# RC_MUX.net
KiCad netlist of a schematic drawn in EAGLE
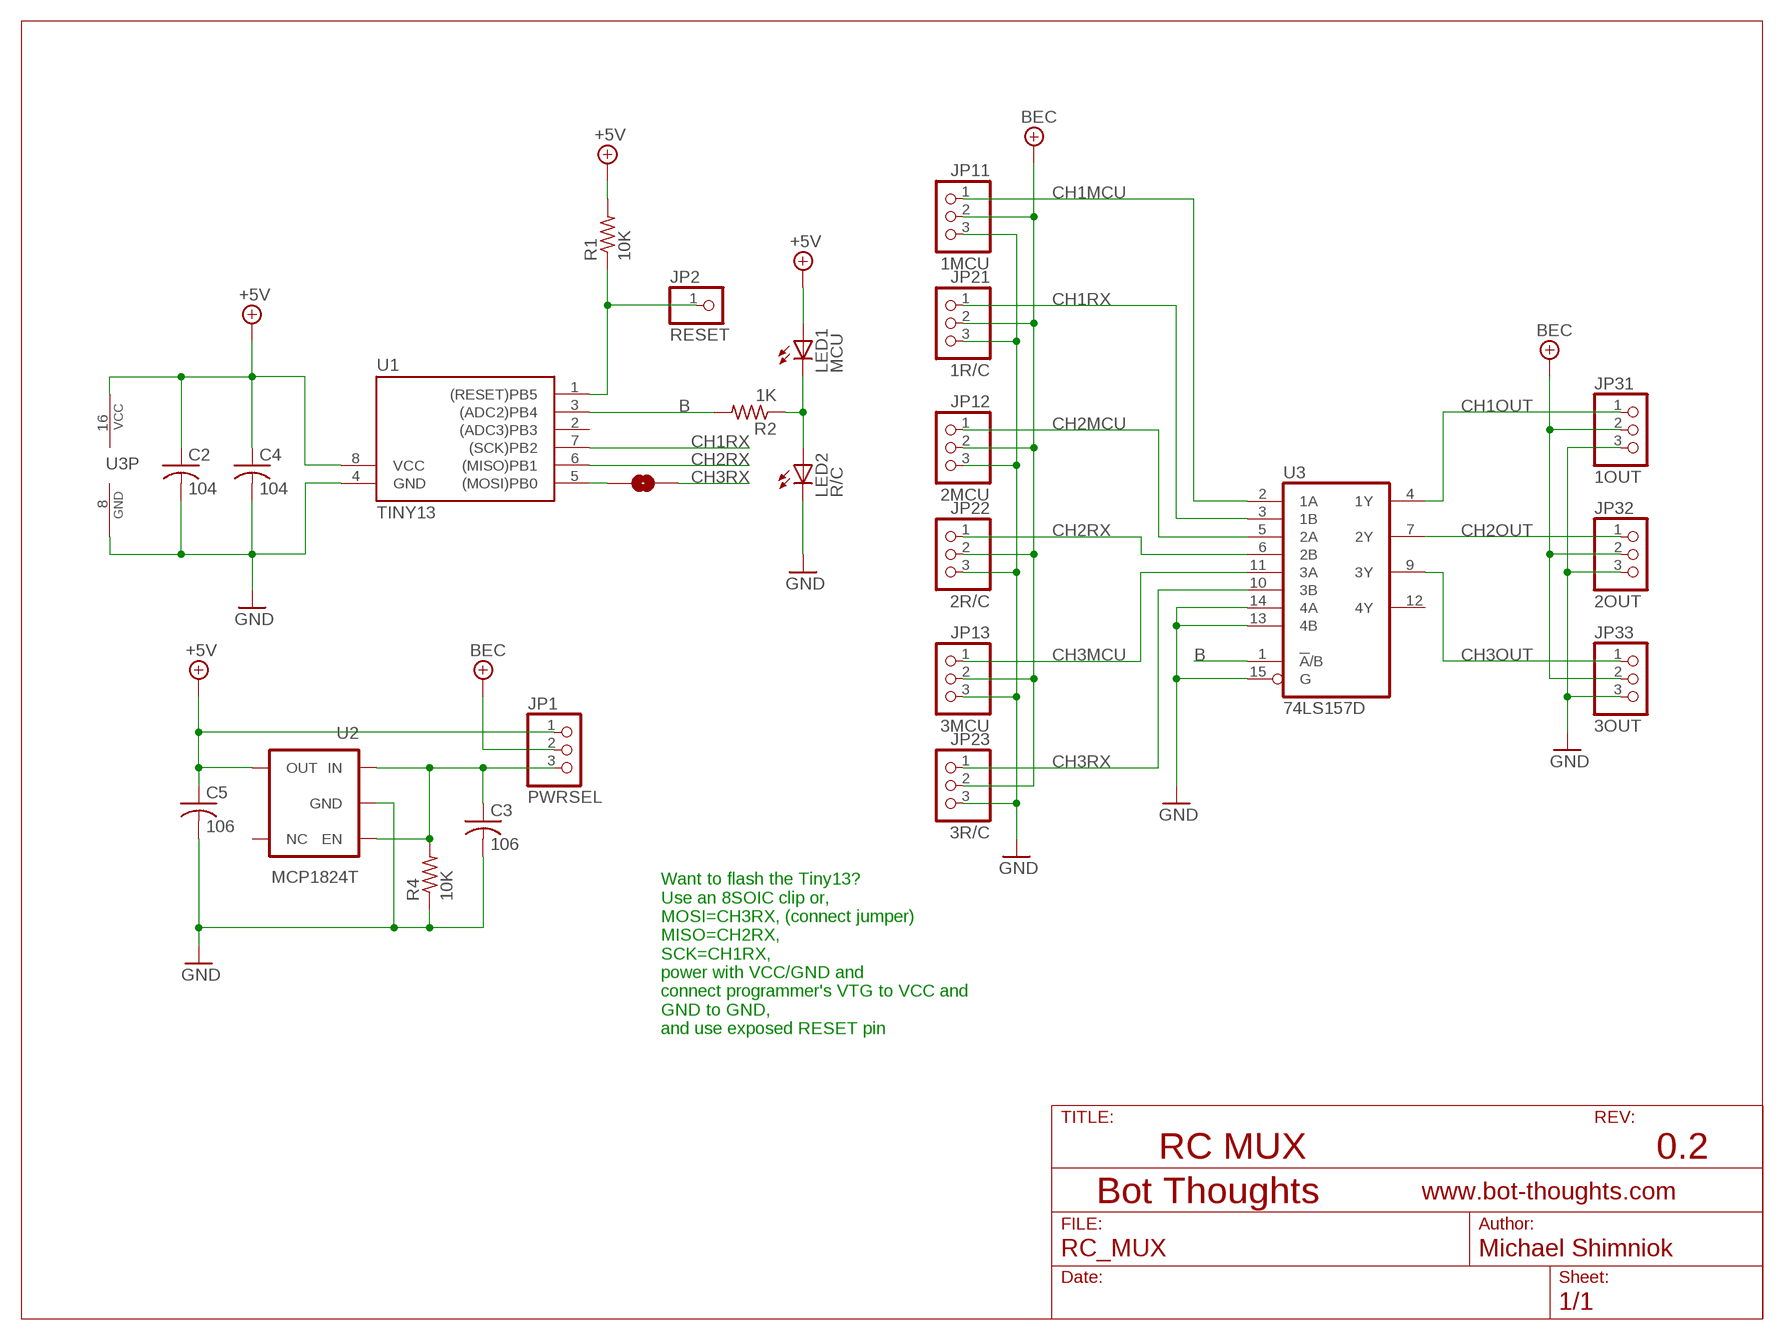
[diagram p0: schematic, sheet 1]

(export (version "E")
  (design (tool "Eeschema 10.0.6"))
  (components
    (comp (ref "C2")
      (value "104")
      (footprint "eagle-import:C0603")
      (fields (field (name "PARTNO") "C1608X7R1E104K080AA"))
      (libsource (lib "eagle-import") (part "C-USC0603"))
    )
    (comp (ref "C3")
      (value "106")
      (footprint "eagle-import:C0603")
      (fields (field (name "PARTNO") "CL10A106MP8NNNC"))
      (libsource (lib "eagle-import") (part "C-USC0603"))
    )
    (comp (ref "C4")
      (value "104")
      (footprint "eagle-import:C0603")
      (fields (field (name "PARTNO") "C1608X7R1E104K080AA"))
      (libsource (lib "eagle-import") (part "C-USC0603"))
    )
    (comp (ref "C5")
      (value "106")
      (footprint "eagle-import:C0603")
      (fields (field (name "PARTNO") "CL10A106MP8NNNC"))
      (libsource (lib "eagle-import") (part "C-USC0603"))
    )
    (comp (ref "JP1")
      (value "PWRSEL")
      (footprint "eagle-import:1X03M")
      (libsource (lib "eagle-import") (part "PINHD-1X03_2.00"))
    )
    (comp (ref "JP2")
      (value "RESET")
      (footprint "eagle-import:1X01-S")
      (libsource (lib "eagle-import") (part "PINHD-1X01_2.54-S"))
    )
    (comp (ref "JP11")
      (value "1MCU")
      (footprint "eagle-import:1X03-S")
      (libsource (lib "eagle-import") (part "PINHD-1X03_2.54-S"))
    )
    (comp (ref "JP12")
      (value "2MCU")
      (footprint "eagle-import:1X03-S")
      (libsource (lib "eagle-import") (part "PINHD-1X03_2.54-S"))
    )
    (comp (ref "JP13")
      (value "3MCU")
      (footprint "eagle-import:1X03-S")
      (libsource (lib "eagle-import") (part "PINHD-1X03_2.54-S"))
    )
    (comp (ref "JP21")
      (value "1R/C")
      (footprint "eagle-import:1X03-S")
      (libsource (lib "eagle-import") (part "PINHD-1X03_2.54-S"))
    )
    (comp (ref "JP22")
      (value "2R/C")
      (footprint "eagle-import:1X03-S")
      (libsource (lib "eagle-import") (part "PINHD-1X03_2.54-S"))
    )
    (comp (ref "JP23")
      (value "3R/C")
      (footprint "eagle-import:1X03-S")
      (libsource (lib "eagle-import") (part "PINHD-1X03_2.54-S"))
    )
    (comp (ref "JP31")
      (value "1OUT")
      (footprint "eagle-import:1X03-S")
      (libsource (lib "eagle-import") (part "PINHD-1X03_2.54-S"))
    )
    (comp (ref "JP32")
      (value "2OUT")
      (footprint "eagle-import:1X03-S")
      (libsource (lib "eagle-import") (part "PINHD-1X03_2.54-S"))
    )
    (comp (ref "JP33")
      (value "3OUT")
      (footprint "eagle-import:1X03-S")
      (libsource (lib "eagle-import") (part "PINHD-1X03_2.54-S"))
    )
    (comp (ref "LED1")
      (value "MCU")
      (footprint "eagle-import:CHIPLED_1206")
      (fields (field (name "PARTNO") "LH N974-KN-1"))
      (libsource (lib "eagle-import") (part "LEDCHIPLED_1206"))
    )
    (comp (ref "LED2")
      (value "R/C")
      (footprint "eagle-import:CHIPLED_1206")
      (fields (field (name "PARTNO") "LG N971-KN-1"))
      (libsource (lib "eagle-import") (part "LEDCHIPLED_1206"))
    )
    (comp (ref "R1")
      (value "10K")
      (footprint "eagle-import:R0603")
      (fields (field (name "PARTNO") "1622829-1"))
      (libsource (lib "eagle-import") (part "R-US_R0603"))
    )
    (comp (ref "R2")
      (value "1K")
      (footprint "eagle-import:R0603")
      (fields (field (name "PARTNO") "RC0603JR-07330RL"))
      (libsource (lib "eagle-import") (part "R-US_R0603"))
    )
    (comp (ref "R4")
      (value "10K")
      (footprint "eagle-import:R0603")
      (fields (field (name "PARTNO") "1622829-1"))
      (libsource (lib "eagle-import") (part "R-US_R0603"))
    )
    (comp (ref "SJ1")
      (value "CH3")
      (footprint "eagle-import:SJ_2S-NOTRACE")
      (libsource (lib "eagle-import") (part "SOLDERJUMPERNC2"))
    )
    (comp (ref "U1")
      (value "TINY13")
      (footprint "eagle-import:SO08")
      (fields (field (name "PARTNO") "ATTINY13A-SSH"))
      (libsource (lib "eagle-import") (part "TINY138S2"))
    )
    (comp (ref "U2")
      (value "MCP1824T")
      (footprint "eagle-import:SOT23-5")
      (fields (field (name "PARTNO") "MCP1824T-5002E/OT"))
      (libsource (lib "eagle-import") (part "MCP1801"))
    )
    (comp (ref "U3")
      (value "74LS157D")
      (footprint "eagle-import:SO16")
      (fields (field (name "PARTNO") "74HCT157D,652"))
      (libsource (lib "eagle-import") (part "74157DLS"))
    )
  )
  (nets
    (net (code "1") (name "+5V") (class "Default")
      (node (ref "C2") (pin "1") (pinfunction "1_1") (pintype "passive"))
      (node (ref "C4") (pin "1") (pinfunction "1_1") (pintype "passive"))
      (node (ref "C5") (pin "1") (pinfunction "1_1") (pintype "passive"))
      (node (ref "JP1") (pin "1") (pinfunction "1_1") (pintype "passive"))
      (node (ref "LED1") (pin "A") (pinfunction "A_A") (pintype "passive"))
      (node (ref "R1") (pin "2") (pinfunction "2_2") (pintype "passive"))
      (node (ref "U1") (pin "8") (pinfunction "VCC_8") (pintype "power_in"))
      (node (ref "U2") (pin "5") (pinfunction "OUT_5") (pintype "passive"))
      (node (ref "U3") (pin "16") (pinfunction "VCC_16") (pintype "power_in"))
    )
    (net (code "2") (name "/B") (class "Default")
      (node (ref "R2") (pin "2") (pinfunction "2_2") (pintype "passive"))
      (node (ref "U1") (pin "3") (pinfunction "(ADC2)PB4_3") (pintype "bidirectional"))
      (node (ref "U3") (pin "1") (pinfunction "~{A}/B_1") (pintype "input"))
    )
    (net (code "3") (name "/CH1MCU") (class "Default")
      (node (ref "JP11") (pin "1") (pinfunction "1_1") (pintype "passive"))
      (node (ref "U3") (pin "2") (pinfunction "1A_2") (pintype "input"))
    )
    (net (code "4") (name "/CH1OUT") (class "Default")
      (node (ref "JP31") (pin "1") (pinfunction "1_1") (pintype "passive"))
      (node (ref "U3") (pin "4") (pinfunction "1Y_4") (pintype "output"))
    )
    (net (code "5") (name "/CH1RX") (class "Default")
      (node (ref "JP21") (pin "1") (pinfunction "1_1") (pintype "passive"))
      (node (ref "U1") (pin "7") (pinfunction "(SCK)PB2_7") (pintype "bidirectional"))
      (node (ref "U3") (pin "3") (pinfunction "1B_3") (pintype "input"))
    )
    (net (code "6") (name "/CH2MCU") (class "Default")
      (node (ref "JP12") (pin "1") (pinfunction "1_1") (pintype "passive"))
      (node (ref "U3") (pin "5") (pinfunction "2A_5") (pintype "input"))
    )
    (net (code "7") (name "/CH2OUT") (class "Default")
      (node (ref "JP32") (pin "1") (pinfunction "1_1") (pintype "passive"))
      (node (ref "U3") (pin "7") (pinfunction "2Y_7") (pintype "output"))
    )
    (net (code "8") (name "/CH2RX") (class "Default")
      (node (ref "JP22") (pin "1") (pinfunction "1_1") (pintype "passive"))
      (node (ref "U1") (pin "6") (pinfunction "(MISO)PB1_6") (pintype "bidirectional"))
      (node (ref "U3") (pin "6") (pinfunction "2B_6") (pintype "input"))
    )
    (net (code "9") (name "/CH3MCU") (class "Default")
      (node (ref "JP13") (pin "1") (pinfunction "1_1") (pintype "passive"))
      (node (ref "U3") (pin "11") (pinfunction "3A_11") (pintype "input"))
    )
    (net (code "10") (name "/CH3OUT") (class "Default")
      (node (ref "JP33") (pin "1") (pinfunction "1_1") (pintype "passive"))
      (node (ref "U3") (pin "9") (pinfunction "3Y_9") (pintype "output"))
    )
    (net (code "11") (name "/CH3RX") (class "Default")
      (node (ref "JP23") (pin "1") (pinfunction "1_1") (pintype "passive"))
      (node (ref "SJ1") (pin "2") (pinfunction "2_2") (pintype "passive"))
      (node (ref "U3") (pin "10") (pinfunction "3B_10") (pintype "input"))
    )
    (net (code "12") (name "BEC") (class "Default")
      (node (ref "JP1") (pin "2") (pinfunction "2_2") (pintype "passive"))
      (node (ref "JP11") (pin "2") (pinfunction "2_2") (pintype "passive"))
      (node (ref "JP12") (pin "2") (pinfunction "2_2") (pintype "passive"))
      (node (ref "JP13") (pin "2") (pinfunction "2_2") (pintype "passive"))
      (node (ref "JP21") (pin "2") (pinfunction "2_2") (pintype "passive"))
      (node (ref "JP22") (pin "2") (pinfunction "2_2") (pintype "passive"))
      (node (ref "JP23") (pin "2") (pinfunction "2_2") (pintype "passive"))
      (node (ref "JP31") (pin "2") (pinfunction "2_2") (pintype "passive"))
      (node (ref "JP32") (pin "2") (pinfunction "2_2") (pintype "passive"))
      (node (ref "JP33") (pin "2") (pinfunction "2_2") (pintype "passive"))
    )
    (net (code "13") (name "GND") (class "Default")
      (node (ref "C2") (pin "2") (pinfunction "2_2") (pintype "passive"))
      (node (ref "C3") (pin "2") (pinfunction "2_2") (pintype "passive"))
      (node (ref "C4") (pin "2") (pinfunction "2_2") (pintype "passive"))
      (node (ref "C5") (pin "2") (pinfunction "2_2") (pintype "passive"))
      (node (ref "JP11") (pin "3") (pinfunction "3_3") (pintype "passive"))
      (node (ref "JP12") (pin "3") (pinfunction "3_3") (pintype "passive"))
      (node (ref "JP13") (pin "3") (pinfunction "3_3") (pintype "passive"))
      (node (ref "JP21") (pin "3") (pinfunction "3_3") (pintype "passive"))
      (node (ref "JP22") (pin "3") (pinfunction "3_3") (pintype "passive"))
      (node (ref "JP23") (pin "3") (pinfunction "3_3") (pintype "passive"))
      (node (ref "JP31") (pin "3") (pinfunction "3_3") (pintype "passive"))
      (node (ref "JP32") (pin "3") (pinfunction "3_3") (pintype "passive"))
      (node (ref "JP33") (pin "3") (pinfunction "3_3") (pintype "passive"))
      (node (ref "LED2") (pin "C") (pinfunction "C_C") (pintype "passive"))
      (node (ref "R4") (pin "1") (pinfunction "1_1") (pintype "passive"))
      (node (ref "U1") (pin "4") (pinfunction "GND_4") (pintype "power_in"))
      (node (ref "U2") (pin "2") (pinfunction "GND_2") (pintype "input"))
      (node (ref "U3") (pin "13") (pinfunction "4B_13") (pintype "input"))
      (node (ref "U3") (pin "14") (pinfunction "4A_14") (pintype "input"))
      (node (ref "U3") (pin "15") (pinfunction "G_15") (pintype "input"))
      (node (ref "U3") (pin "8") (pinfunction "GND_8") (pintype "power_in"))
    )
    (net (code "14") (name "Net-(LED1-PadC)") (class "Default")
      (node (ref "LED1") (pin "C") (pinfunction "C_C") (pintype "passive"))
      (node (ref "LED2") (pin "A") (pinfunction "A_A") (pintype "passive"))
      (node (ref "R2") (pin "1") (pinfunction "1_1") (pintype "passive"))
    )
    (net (code "15") (name "Net-(U1-(MOSI)PB0)") (class "Default")
      (node (ref "SJ1") (pin "1") (pinfunction "1_1") (pintype "passive"))
      (node (ref "U1") (pin "5") (pinfunction "(MOSI)PB0_5") (pintype "bidirectional"))
    )
    (net (code "16") (name "Net-(U1-(RESET)PB5)") (class "Default")
      (node (ref "JP2") (pin "1") (pinfunction "1_1") (pintype "passive"))
      (node (ref "R1") (pin "1") (pinfunction "1_1") (pintype "passive"))
      (node (ref "U1") (pin "1") (pinfunction "(RESET)PB5_1") (pintype "bidirectional"))
    )
    (net (code "17") (name "Net-(U2-EN)") (class "Default")
      (node (ref "C3") (pin "1") (pinfunction "1_1") (pintype "passive"))
      (node (ref "JP1") (pin "3") (pinfunction "3_3") (pintype "passive"))
      (node (ref "R4") (pin "2") (pinfunction "2_2") (pintype "passive"))
      (node (ref "U2") (pin "1") (pinfunction "IN_1") (pintype "input"))
      (node (ref "U2") (pin "3") (pinfunction "EN_3") (pintype "input"))
    )
    (net (code "18") (name "unconnected-(U1-(ADC3)PB3-Pad2)") (class "Default")
      (node (ref "U1") (pin "2") (pinfunction "(ADC3)PB3_2") (pintype "bidirectional"))
    )
    (net (code "19") (name "unconnected-(U2-NC-Pad4)") (class "Default")
      (node (ref "U2") (pin "4") (pinfunction "NC_4") (pintype "input"))
    )
    (net (code "20") (name "unconnected-(U3A-4Y-Pad12)") (class "Default")
      (node (ref "U3") (pin "12") (pinfunction "4Y_12") (pintype "output"))
    )
  )
)
